# MAX30003.net
KiCad netlist of a schematic drawn in Altium Designer
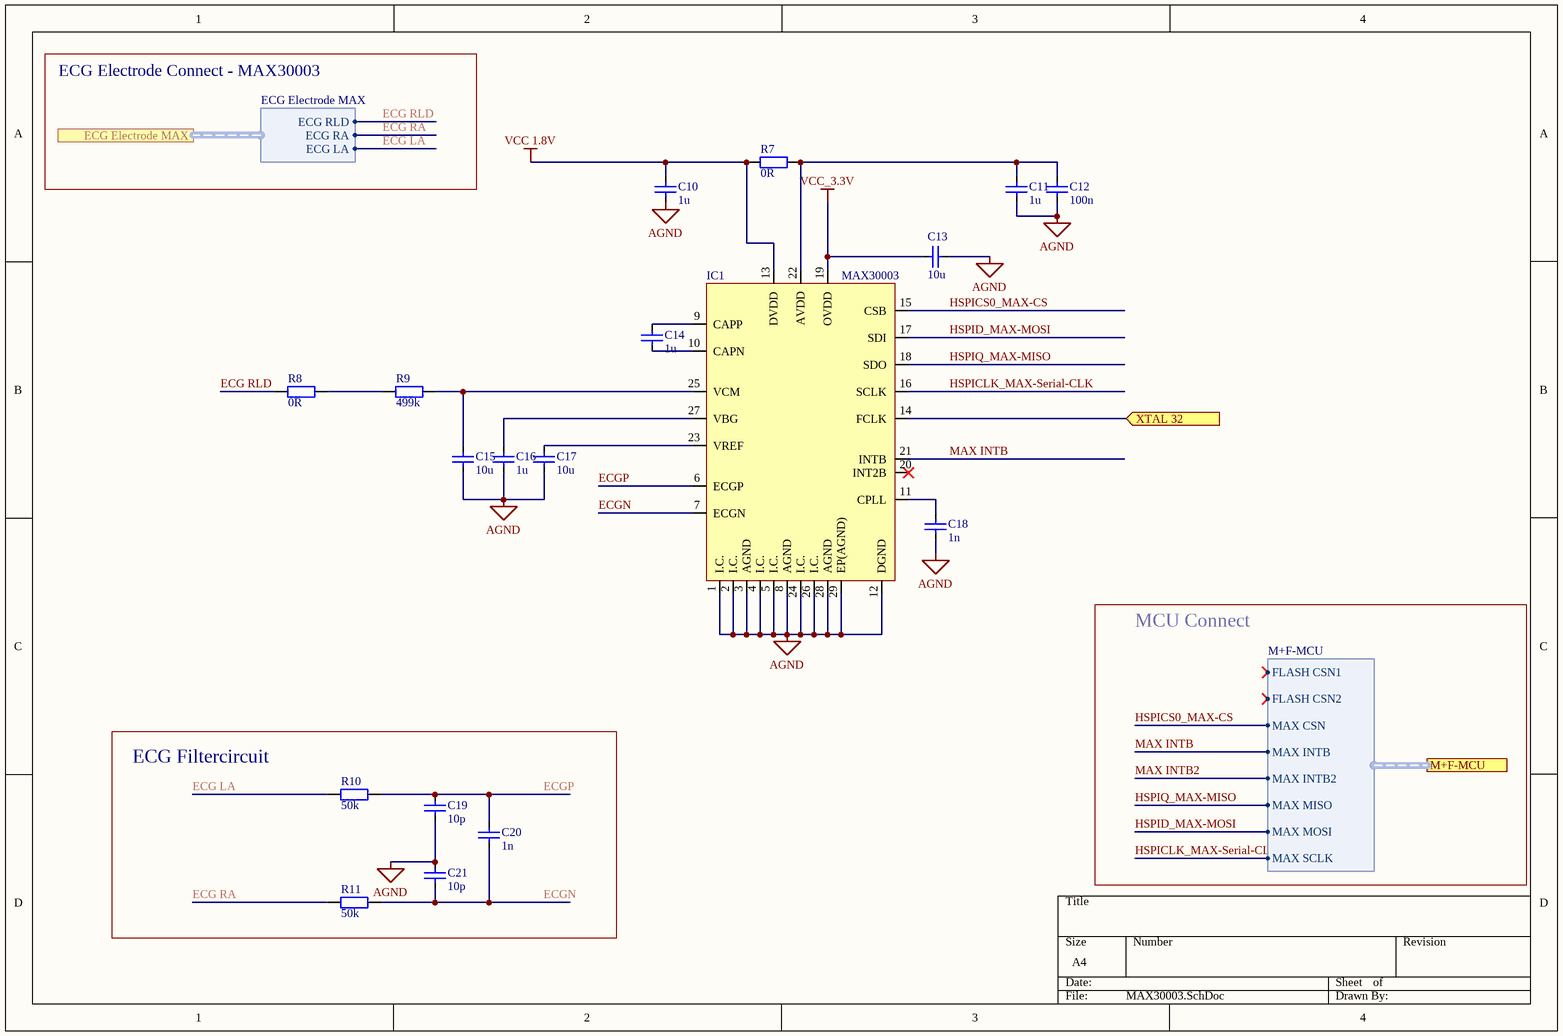
[diagram p0: MAX30003.SchDoc]

(export (version "E")
  (design (tool "Eeschema 10.0.6"))
  (components
    (comp (ref "C10")
      (value "1u")
      (footprint "Lib_C:CAPC1005X03N")
      (description "Kondensator 1u 6V3 0402")
      (libsource (lib "Lib_C") (part "C_1u_6V3_0402"))
    )
    (comp (ref "C11")
      (value "1u")
      (footprint "Lib_C:CAPC1005X03N")
      (description "Kondensator 1u 6V3 0402")
      (libsource (lib "Lib_C") (part "C_1u_6V3_0402"))
    )
    (comp (ref "C12")
      (value "100n")
      (footprint "Lib_C:CAPC1005X03N")
      (description "Kondensator 100n 50V 0402")
      (libsource (lib "Lib_C") (part "C_100n_50V_0402"))
    )
    (comp (ref "C13")
      (value "10u")
      (footprint "Lib_C:CAPC1608X05N")
      (description "Kondensator 10u 10V 0603")
      (libsource (lib "Lib_C") (part "C_10u_10V_0603"))
    )
    (comp (ref "C14")
      (value "1u")
      (footprint "Lib_C:CAPC1005X03N")
      (description "Kondensator 1u 6V3 0402")
      (libsource (lib "Lib_C") (part "C_1u_6V3_0402"))
    )
    (comp (ref "C15")
      (value "10u")
      (footprint "Lib_C:CAPC1608X05N")
      (description "Kondensator 10u 10V 0603")
      (libsource (lib "Lib_C") (part "C_10u_10V_0603"))
    )
    (comp (ref "C16")
      (value "1u")
      (footprint "Lib_C:CAPC1005X03N")
      (description "Kondensator 1u 6V3 0402")
      (libsource (lib "Lib_C") (part "C_1u_6V3_0402"))
    )
    (comp (ref "C17")
      (value "10u")
      (footprint "Lib_C:CAPC1608X05N")
      (description "Kondensator 10u 10V 0603")
      (libsource (lib "Lib_C") (part "C_10u_10V_0603"))
    )
    (comp (ref "C18")
      (value "1n")
      (footprint "Lib_C:CAPC1005X03N")
      (description "Kondensator 1n 50V 0402")
      (libsource (lib "Lib_C") (part "C_1n_50V_0402"))
    )
    (comp (ref "C19")
      (value "10p")
      (footprint "Lib_C:CAPC1005X03N")
      (description "Kondensator 10p 25V NP0 0402")
      (libsource (lib "Lib_C") (part "C_10p_25V_NP0_0402"))
    )
    (comp (ref "C20")
      (value "1n")
      (footprint "Lib_C:CAPC1005X03N")
      (description "Kondensator 1n 50V 0402")
      (libsource (lib "Lib_C") (part "C_1n_50V_0402"))
    )
    (comp (ref "C21")
      (value "10p")
      (footprint "Lib_C:CAPC1005X03N")
      (description "Kondensator 10p 25V NP0 0402")
      (libsource (lib "Lib_C") (part "C_10p_25V_NP0_0402"))
    )
    (comp (ref "IC1")
      (value "MAX30003")
      (footprint "MAX30003CTI+T2855-8")
      (libsource (lib "Lib_IC") (part "MAX30003CTI+"))
    )
    (comp (ref "R7")
      (value "0R")
      (footprint "Lib_R:RESC1005X03N")
      (description "Widerstand 0R 0402")
      (libsource (lib "Lib_R") (part "R_0R_0402"))
    )
    (comp (ref "R8")
      (value "0R")
      (footprint "Lib_R:RESC1005X03N")
      (description "Widerstand 0R 0402")
      (libsource (lib "Lib_R") (part "R_0R_0402"))
    )
    (comp (ref "R9")
      (value "499k")
      (footprint "Lib_R:RESC1005X03N")
      (description "Widerstand 0402")
      (libsource (lib "Lib_R") (part "R_0402"))
    )
    (comp (ref "R10")
      (value "50k")
      (footprint "Lib_R:RESC1005X03N")
      (description "Widerstand 50k 0402")
      (libsource (lib "Lib_R") (part "R_0R_0402"))
    )
    (comp (ref "R11")
      (value "50k")
      (footprint "Lib_R:RESC1005X03N")
      (description "Widerstand 50k 0402")
      (libsource (lib "Lib_R") (part "R_0R_0402"))
    )
  )
  (nets
    (net (code "5") (name "/ECG LA") (class "Default")
      (node (ref "R10") (pin "1") (pinfunction "1_1") (pintype "passive"))
    )
    (net (code "6") (name "/ECG RA") (class "Default")
      (node (ref "R11") (pin "1") (pinfunction "1_1") (pintype "passive"))
    )
    (net (code "7") (name "/ECG RLD") (class "Default")
      (node (ref "R8") (pin "1") (pinfunction "1_1") (pintype "passive"))
    )
    (net (code "8") (name "/ECGN") (class "Default")
      (node (ref "C20") (pin "1") (pinfunction "1_1") (pintype "passive"))
      (node (ref "C21") (pin "1") (pinfunction "1_1") (pintype "passive"))
      (node (ref "IC1") (pin "7") (pinfunction "ECGN_7") (pintype "passive"))
      (node (ref "R11") (pin "2") (pinfunction "2_2") (pintype "passive"))
    )
    (net (code "9") (name "/ECGP") (class "Default")
      (node (ref "C19") (pin "2") (pinfunction "2_2") (pintype "passive"))
      (node (ref "C20") (pin "2") (pinfunction "2_2") (pintype "passive"))
      (node (ref "IC1") (pin "6") (pinfunction "ECGP_6") (pintype "passive"))
      (node (ref "R10") (pin "2") (pinfunction "2_2") (pintype "passive"))
    )
    (net (code "10") (name "/HSPICLK_MAX-Serial-CLK") (class "Default")
      (node (ref "IC1") (pin "16") (pinfunction "SCLK_16") (pintype "passive"))
    )
    (net (code "11") (name "/HSPICS0_MAX-CS") (class "Default")
      (node (ref "IC1") (pin "15") (pinfunction "CSB_15") (pintype "passive"))
    )
    (net (code "12") (name "/HSPID_MAX-MOSI") (class "Default")
      (node (ref "IC1") (pin "17") (pinfunction "SDI_17") (pintype "passive"))
    )
    (net (code "13") (name "/HSPIQ_MAX-MISO") (class "Default")
      (node (ref "IC1") (pin "18") (pinfunction "SDO_18") (pintype "passive"))
    )
    (net (code "14") (name "/MAX INTB") (class "Default")
      (node (ref "IC1") (pin "21") (pinfunction "INTB_21") (pintype "passive"))
    )
    (net (code "16") (name "/XTAL 32") (class "Default")
      (node (ref "IC1") (pin "14") (pinfunction "FCLK_14") (pintype "passive"))
    )
    (net (code "19") (name "AGND") (class "Default")
      (node (ref "C10") (pin "1") (pinfunction "1_1") (pintype "passive"))
      (node (ref "C11") (pin "1") (pinfunction "1_1") (pintype "passive"))
      (node (ref "C12") (pin "1") (pinfunction "1_1") (pintype "passive"))
      (node (ref "C13") (pin "2") (pinfunction "2_2") (pintype "passive"))
      (node (ref "C15") (pin "1") (pinfunction "1_1") (pintype "passive"))
      (node (ref "C16") (pin "1") (pinfunction "1_1") (pintype "passive"))
      (node (ref "C17") (pin "1") (pinfunction "1_1") (pintype "passive"))
      (node (ref "C18") (pin "1") (pinfunction "1_1") (pintype "passive"))
      (node (ref "C19") (pin "1") (pinfunction "1_1") (pintype "passive"))
      (node (ref "C21") (pin "2") (pinfunction "2_2") (pintype "passive"))
      (node (ref "IC1") (pin "1") (pinfunction "I.C._1") (pintype "passive"))
      (node (ref "IC1") (pin "12") (pinfunction "DGND_12") (pintype "passive"))
      (node (ref "IC1") (pin "2") (pinfunction "I.C._2") (pintype "passive"))
      (node (ref "IC1") (pin "24") (pinfunction "I.C._24") (pintype "passive"))
      (node (ref "IC1") (pin "26") (pinfunction "I.C._26") (pintype "passive"))
      (node (ref "IC1") (pin "28") (pinfunction "AGND_28") (pintype "passive"))
      (node (ref "IC1") (pin "29") (pinfunction "EP(AGND)_29") (pintype "passive"))
      (node (ref "IC1") (pin "3") (pinfunction "AGND_3") (pintype "passive"))
      (node (ref "IC1") (pin "4") (pinfunction "I.C._4") (pintype "passive"))
      (node (ref "IC1") (pin "5") (pinfunction "I.C._5") (pintype "passive"))
      (node (ref "IC1") (pin "8") (pinfunction "AGND_8") (pintype "passive"))
    )
    (net (code "20") (name "Net-(IC1-AVDD)") (class "Default")
      (node (ref "C11") (pin "2") (pinfunction "2_2") (pintype "passive"))
      (node (ref "C12") (pin "2") (pinfunction "2_2") (pintype "passive"))
      (node (ref "IC1") (pin "22") (pinfunction "AVDD_22") (pintype "passive"))
      (node (ref "R7") (pin "2") (pinfunction "2_2") (pintype "passive"))
    )
    (net (code "21") (name "Net-(IC1-CAPN)") (class "Default")
      (node (ref "C14") (pin "1") (pinfunction "1_1") (pintype "passive"))
      (node (ref "IC1") (pin "10") (pinfunction "CAPN_10") (pintype "passive"))
    )
    (net (code "22") (name "Net-(IC1-CAPP)") (class "Default")
      (node (ref "C14") (pin "2") (pinfunction "2_2") (pintype "passive"))
      (node (ref "IC1") (pin "9") (pinfunction "CAPP_9") (pintype "passive"))
    )
    (net (code "23") (name "Net-(IC1-CPLL)") (class "Default")
      (node (ref "C18") (pin "2") (pinfunction "2_2") (pintype "passive"))
      (node (ref "IC1") (pin "11") (pinfunction "CPLL_11") (pintype "passive"))
    )
    (net (code "24") (name "Net-(IC1-VBG)") (class "Default")
      (node (ref "C16") (pin "2") (pinfunction "2_2") (pintype "passive"))
      (node (ref "IC1") (pin "27") (pinfunction "VBG_27") (pintype "passive"))
    )
    (net (code "25") (name "Net-(IC1-VCM)") (class "Default")
      (node (ref "C15") (pin "2") (pinfunction "2_2") (pintype "passive"))
      (node (ref "IC1") (pin "25") (pinfunction "VCM_25") (pintype "passive"))
      (node (ref "R9") (pin "2") (pinfunction "2_2") (pintype "passive"))
    )
    (net (code "26") (name "Net-(IC1-VREF)") (class "Default")
      (node (ref "C17") (pin "2") (pinfunction "2_2") (pintype "passive"))
      (node (ref "IC1") (pin "23") (pinfunction "VREF_23") (pintype "passive"))
    )
    (net (code "27") (name "Net-(R8-Pad2)") (class "Default")
      (node (ref "R8") (pin "2") (pinfunction "2_2") (pintype "passive"))
      (node (ref "R9") (pin "1") (pinfunction "1_1") (pintype "passive"))
    )
    (net (code "28") (name "VCC 1.8V") (class "Default")
      (node (ref "C10") (pin "2") (pinfunction "2_2") (pintype "passive"))
      (node (ref "IC1") (pin "13") (pinfunction "DVDD_13") (pintype "passive"))
      (node (ref "R7") (pin "1") (pinfunction "1_1") (pintype "passive"))
    )
    (net (code "29") (name "VCC_3.3V") (class "Default")
      (node (ref "C13") (pin "1") (pinfunction "1_1") (pintype "passive"))
      (node (ref "IC1") (pin "19") (pinfunction "OVDD_19") (pintype "passive"))
    )
    (net (code "30") (name "unconnected-(IC1-INT2B-Pad20)") (class "Default")
      (node (ref "IC1") (pin "20") (pinfunction "INT2B_20") (pintype "passive+no_connect"))
    )
  )
)
